# powerSupply.net
KiCad netlist of a schematic drawn in EAGLE
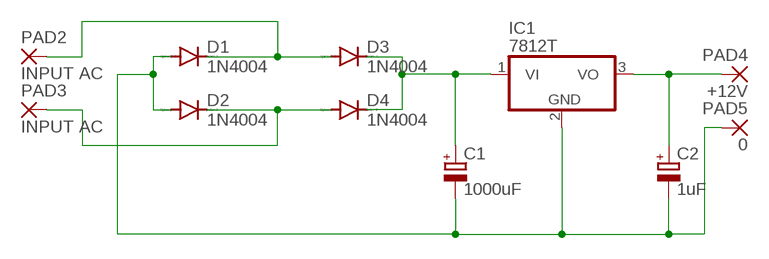
[diagram p0: schematic, sheet 1]

(export (version "E")
  (design (tool "Eeschema 10.0.6"))
  (components
    (comp (ref "C1")
      (value "1000uF")
      (footprint "eagle-import:E3,5-10")
      (libsource (lib "eagle-import") (part "CPOL-EUE3.5-10"))
    )
    (comp (ref "C2")
      (value "1uF")
      (footprint "eagle-import:E2,5-5")
      (libsource (lib "eagle-import") (part "CPOL-EUE2.5-5"))
    )
    (comp (ref "D1")
      (value "1N4004")
      (footprint "eagle-import:DO41-10")
      (libsource (lib "eagle-import") (part "1N4004"))
    )
    (comp (ref "D2")
      (value "1N4004")
      (footprint "eagle-import:DO41-10")
      (libsource (lib "eagle-import") (part "1N4004"))
    )
    (comp (ref "D3")
      (value "1N4004")
      (footprint "eagle-import:DO41-10")
      (libsource (lib "eagle-import") (part "1N4004"))
    )
    (comp (ref "D4")
      (value "1N4004")
      (footprint "eagle-import:DO41-10")
      (libsource (lib "eagle-import") (part "1N4004"))
    )
    (comp (ref "IC1")
      (value "7812T")
      (footprint "eagle-import:TO220H")
      (libsource (lib "eagle-import") (part "78T12"))
    )
    (comp (ref "PAD2")
      (value "INPUT AC")
      (footprint "eagle-import:2,54_1,0")
      (libsource (lib "eagle-import") (part "2,54/1,0"))
    )
    (comp (ref "PAD3")
      (value "INPUT AC")
      (footprint "eagle-import:2,54_1,0")
      (libsource (lib "eagle-import") (part "2,54/1,0"))
    )
    (comp (ref "PAD4")
      (value "+12V")
      (footprint "eagle-import:2,54_1,0")
      (libsource (lib "eagle-import") (part "2,54/1,0"))
    )
    (comp (ref "PAD5")
      (value "0")
      (footprint "eagle-import:2,54_1,0")
      (libsource (lib "eagle-import") (part "2,54/1,0"))
    )
  )
  (nets
    (net (code "1") (name "Net-(IC1-GND)") (class "Default")
      (node (ref "C1") (pin "-") (pinfunction "-_-") (pintype "passive"))
      (node (ref "C2") (pin "-") (pinfunction "-_-") (pintype "passive"))
      (node (ref "D1") (pin "A") (pinfunction "A_A") (pintype "passive"))
      (node (ref "D2") (pin "A") (pinfunction "A_A") (pintype "passive"))
      (node (ref "IC1") (pin "2") (pinfunction "GND_2") (pintype "passive"))
      (node (ref "PAD5") (pin "1") (pinfunction "P_1") (pintype "passive"))
    )
    (net (code "2") (name "Net-(IC1-VI)") (class "Default")
      (node (ref "C1") (pin "+") (pinfunction "+_+") (pintype "passive"))
      (node (ref "D3") (pin "C") (pinfunction "C_C") (pintype "passive"))
      (node (ref "D4") (pin "C") (pinfunction "C_C") (pintype "passive"))
      (node (ref "IC1") (pin "1") (pinfunction "VI_1") (pintype "input"))
    )
    (net (code "3") (name "Net-(IC1-VO)") (class "Default")
      (node (ref "C2") (pin "+") (pinfunction "+_+") (pintype "passive"))
      (node (ref "IC1") (pin "3") (pinfunction "VO_3") (pintype "passive"))
      (node (ref "PAD4") (pin "1") (pinfunction "P_1") (pintype "passive"))
    )
    (net (code "4") (name "Net-(PAD2-P)") (class "Default")
      (node (ref "D1") (pin "C") (pinfunction "C_C") (pintype "passive"))
      (node (ref "D3") (pin "A") (pinfunction "A_A") (pintype "passive"))
      (node (ref "PAD2") (pin "1") (pinfunction "P_1") (pintype "passive"))
    )
    (net (code "5") (name "Net-(PAD3-P)") (class "Default")
      (node (ref "D2") (pin "C") (pinfunction "C_C") (pintype "passive"))
      (node (ref "D4") (pin "A") (pinfunction "A_A") (pintype "passive"))
      (node (ref "PAD3") (pin "1") (pinfunction "P_1") (pintype "passive"))
    )
  )
)
